# Rene_Panel_schematic.net
KiCad netlist of a schematic drawn in Altium Designer
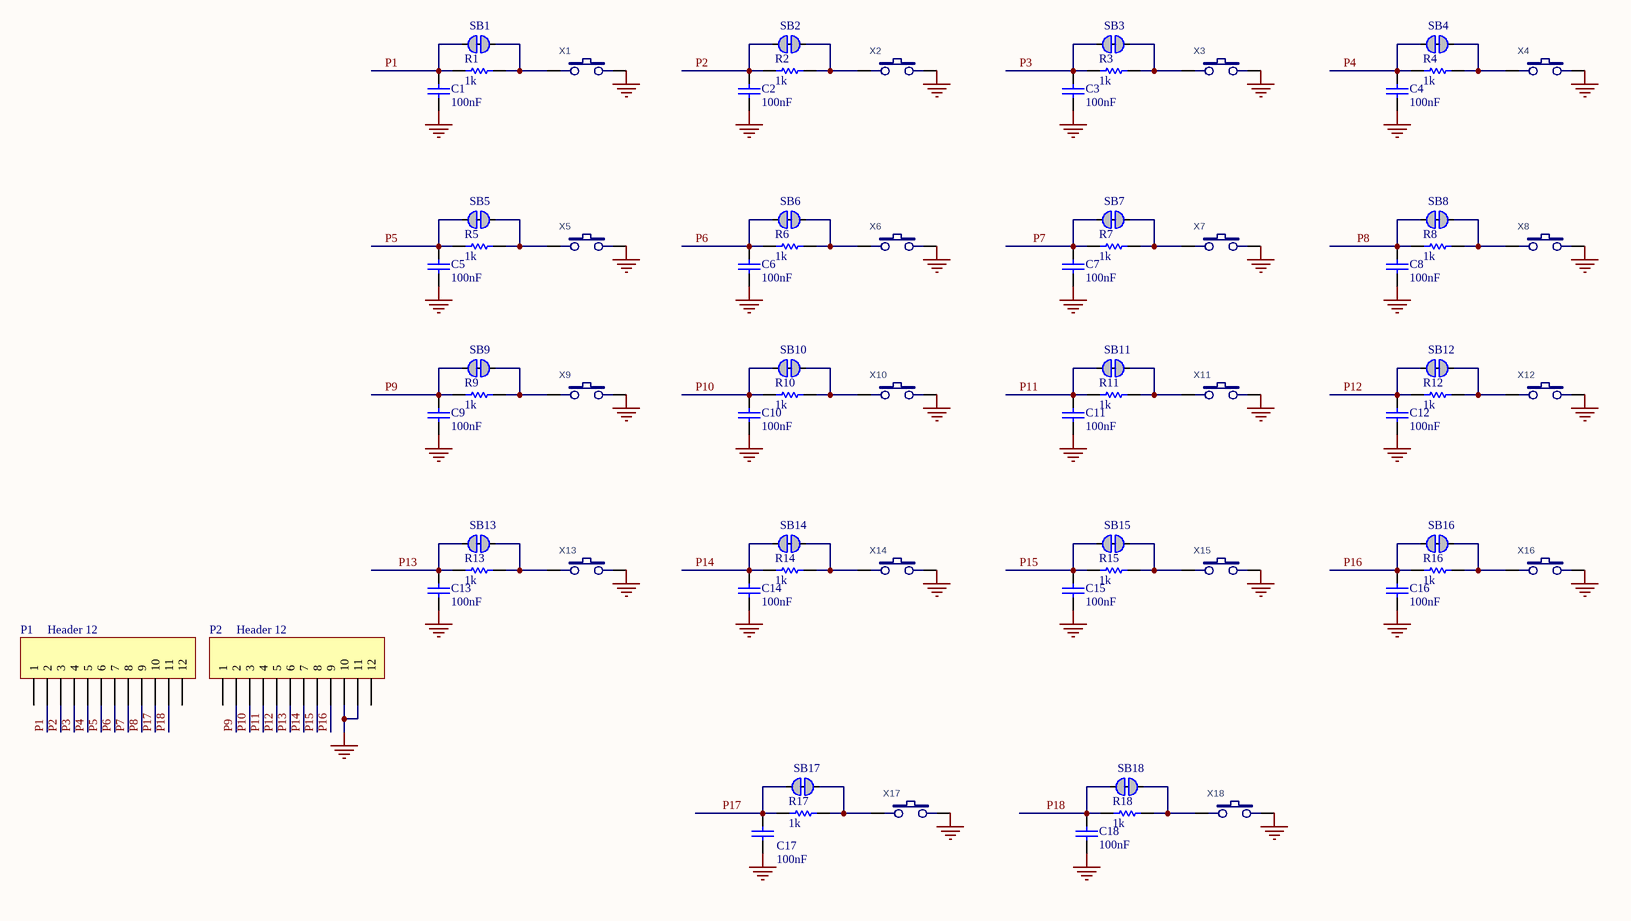
[diagram p0: Rene_Panel_schematic.SchDoc]

(export (version "E")
  (design (tool "Eeschema 10.0.6"))
  (components
    (comp (ref "C1")
      (value "100nF")
      (footprint "myParts:CAPA_0805")
      (description "100nF 0805")
      (fields (field (name "PARTNUMBER") "885012207072"))
      (libsource (lib "myParts") (part "Capacitor"))
    )
    (comp (ref "C2")
      (value "100nF")
      (footprint "myParts:CAPA_0805")
      (description "100nF 0805")
      (fields (field (name "PARTNUMBER") "885012207072"))
      (libsource (lib "myParts") (part "Capacitor"))
    )
    (comp (ref "C3")
      (value "100nF")
      (footprint "myParts:CAPA_0805")
      (description "100nF 0805")
      (fields (field (name "PARTNUMBER") "885012207072"))
      (libsource (lib "myParts") (part "Capacitor"))
    )
    (comp (ref "C4")
      (value "100nF")
      (footprint "myParts:CAPA_0805")
      (description "100nF 0805")
      (fields (field (name "PARTNUMBER") "885012207072"))
      (libsource (lib "myParts") (part "Capacitor"))
    )
    (comp (ref "C5")
      (value "100nF")
      (footprint "myParts:CAPA_0805")
      (description "100nF 0805")
      (fields (field (name "PARTNUMBER") "885012207072"))
      (libsource (lib "myParts") (part "Capacitor"))
    )
    (comp (ref "C6")
      (value "100nF")
      (footprint "myParts:CAPA_0805")
      (description "100nF 0805")
      (fields (field (name "PARTNUMBER") "885012207072"))
      (libsource (lib "myParts") (part "Capacitor"))
    )
    (comp (ref "C7")
      (value "100nF")
      (footprint "myParts:CAPA_0805")
      (description "100nF 0805")
      (fields (field (name "PARTNUMBER") "885012207072"))
      (libsource (lib "myParts") (part "Capacitor"))
    )
    (comp (ref "C8")
      (value "100nF")
      (footprint "myParts:CAPA_0805")
      (description "100nF 0805")
      (fields (field (name "PARTNUMBER") "885012207072"))
      (libsource (lib "myParts") (part "Capacitor"))
    )
    (comp (ref "C9")
      (value "100nF")
      (footprint "myParts:CAPA_0805")
      (description "100nF 0805")
      (fields (field (name "PARTNUMBER") "885012207072"))
      (libsource (lib "myParts") (part "Capacitor"))
    )
    (comp (ref "C10")
      (value "100nF")
      (footprint "myParts:CAPA_0805")
      (description "100nF 0805")
      (fields (field (name "PARTNUMBER") "885012207072"))
      (libsource (lib "myParts") (part "Capacitor"))
    )
    (comp (ref "C11")
      (value "100nF")
      (footprint "myParts:CAPA_0805")
      (description "100nF 0805")
      (fields (field (name "PARTNUMBER") "885012207072"))
      (libsource (lib "myParts") (part "Capacitor"))
    )
    (comp (ref "C12")
      (value "100nF")
      (footprint "myParts:CAPA_0805")
      (description "100nF 0805")
      (fields (field (name "PARTNUMBER") "885012207072"))
      (libsource (lib "myParts") (part "Capacitor"))
    )
    (comp (ref "C13")
      (value "100nF")
      (footprint "myParts:CAPA_0805")
      (description "100nF 0805")
      (fields (field (name "PARTNUMBER") "885012207072"))
      (libsource (lib "myParts") (part "Capacitor"))
    )
    (comp (ref "C14")
      (value "100nF")
      (footprint "myParts:CAPA_0805")
      (description "100nF 0805")
      (fields (field (name "PARTNUMBER") "885012207072"))
      (libsource (lib "myParts") (part "Capacitor"))
    )
    (comp (ref "C15")
      (value "100nF")
      (footprint "myParts:CAPA_0805")
      (description "100nF 0805")
      (fields (field (name "PARTNUMBER") "885012207072"))
      (libsource (lib "myParts") (part "Capacitor"))
    )
    (comp (ref "C16")
      (value "100nF")
      (footprint "myParts:CAPA_0805")
      (description "100nF 0805")
      (fields (field (name "PARTNUMBER") "885012207072"))
      (libsource (lib "myParts") (part "Capacitor"))
    )
    (comp (ref "C17")
      (value "100nF")
      (footprint "myParts:CAPA_0805")
      (description "100nF 0805")
      (fields (field (name "PARTNUMBER") "885012207072"))
      (libsource (lib "myParts") (part "Capacitor"))
    )
    (comp (ref "C18")
      (value "100nF")
      (footprint "myParts:CAPA_0805")
      (description "100nF 0805")
      (fields (field (name "PARTNUMBER") "885012207072"))
      (libsource (lib "myParts") (part "Capacitor"))
    )
    (comp (ref "P1")
      (value "Header 12")
      (footprint "myParts:LIST_1x12_SMD")
      (description "Header, 12-Pin")
      (fields (field (name "PUBLISHER") "Altium Limited"))
      (libsource (lib "Miscellaneous Connectors") (part "Header 12"))
    )
    (comp (ref "P2")
      (value "Header 12")
      (footprint "myParts:LIST_1x12_SMD")
      (description "Header, 12-Pin")
      (fields (field (name "PUBLISHER") "Altium Limited"))
      (libsource (lib "Miscellaneous Connectors") (part "Header 12"))
    )
    (comp (ref "R1")
      (value "1k")
      (footprint "myParts:RES_0805")
      (description "10k 0805")
      (fields (field (name "PARTNUMBER") "RR1220P-103-D") (field (name "MANUFACTURER") "Susumu"))
      (libsource (lib "myParts") (part "Resistor"))
    )
    (comp (ref "R2")
      (value "1k")
      (footprint "myParts:RES_0805")
      (description "10k 0805")
      (fields (field (name "PARTNUMBER") "RR1220P-103-D") (field (name "MANUFACTURER") "Susumu"))
      (libsource (lib "myParts") (part "Resistor"))
    )
    (comp (ref "R3")
      (value "1k")
      (footprint "myParts:RES_0805")
      (description "10k 0805")
      (fields (field (name "PARTNUMBER") "RR1220P-103-D") (field (name "MANUFACTURER") "Susumu"))
      (libsource (lib "myParts") (part "Resistor"))
    )
    (comp (ref "R4")
      (value "1k")
      (footprint "myParts:RES_0805")
      (description "10k 0805")
      (fields (field (name "PARTNUMBER") "RR1220P-103-D") (field (name "MANUFACTURER") "Susumu"))
      (libsource (lib "myParts") (part "Resistor"))
    )
    (comp (ref "R5")
      (value "1k")
      (footprint "myParts:RES_0805")
      (description "10k 0805")
      (fields (field (name "PARTNUMBER") "RR1220P-103-D") (field (name "MANUFACTURER") "Susumu"))
      (libsource (lib "myParts") (part "Resistor"))
    )
    (comp (ref "R6")
      (value "1k")
      (footprint "myParts:RES_0805")
      (description "10k 0805")
      (fields (field (name "PARTNUMBER") "RR1220P-103-D") (field (name "MANUFACTURER") "Susumu"))
      (libsource (lib "myParts") (part "Resistor"))
    )
    (comp (ref "R7")
      (value "1k")
      (footprint "myParts:RES_0805")
      (description "10k 0805")
      (fields (field (name "PARTNUMBER") "RR1220P-103-D") (field (name "MANUFACTURER") "Susumu"))
      (libsource (lib "myParts") (part "Resistor"))
    )
    (comp (ref "R8")
      (value "1k")
      (footprint "myParts:RES_0805")
      (description "10k 0805")
      (fields (field (name "PARTNUMBER") "RR1220P-103-D") (field (name "MANUFACTURER") "Susumu"))
      (libsource (lib "myParts") (part "Resistor"))
    )
    (comp (ref "R9")
      (value "1k")
      (footprint "myParts:RES_0805")
      (description "10k 0805")
      (fields (field (name "PARTNUMBER") "RR1220P-103-D") (field (name "MANUFACTURER") "Susumu"))
      (libsource (lib "myParts") (part "Resistor"))
    )
    (comp (ref "R10")
      (value "1k")
      (footprint "myParts:RES_0805")
      (description "10k 0805")
      (fields (field (name "PARTNUMBER") "RR1220P-103-D") (field (name "MANUFACTURER") "Susumu"))
      (libsource (lib "myParts") (part "Resistor"))
    )
    (comp (ref "R11")
      (value "1k")
      (footprint "myParts:RES_0805")
      (description "10k 0805")
      (fields (field (name "PARTNUMBER") "RR1220P-103-D") (field (name "MANUFACTURER") "Susumu"))
      (libsource (lib "myParts") (part "Resistor"))
    )
    (comp (ref "R12")
      (value "1k")
      (footprint "myParts:RES_0805")
      (description "10k 0805")
      (fields (field (name "PARTNUMBER") "RR1220P-103-D") (field (name "MANUFACTURER") "Susumu"))
      (libsource (lib "myParts") (part "Resistor"))
    )
    (comp (ref "R13")
      (value "1k")
      (footprint "myParts:RES_0805")
      (description "10k 0805")
      (fields (field (name "PARTNUMBER") "RR1220P-103-D") (field (name "MANUFACTURER") "Susumu"))
      (libsource (lib "myParts") (part "Resistor"))
    )
    (comp (ref "R14")
      (value "1k")
      (footprint "myParts:RES_0805")
      (description "10k 0805")
      (fields (field (name "PARTNUMBER") "RR1220P-103-D") (field (name "MANUFACTURER") "Susumu"))
      (libsource (lib "myParts") (part "Resistor"))
    )
    (comp (ref "R15")
      (value "1k")
      (footprint "myParts:RES_0805")
      (description "10k 0805")
      (fields (field (name "PARTNUMBER") "RR1220P-103-D") (field (name "MANUFACTURER") "Susumu"))
      (libsource (lib "myParts") (part "Resistor"))
    )
    (comp (ref "R16")
      (value "1k")
      (footprint "myParts:RES_0805")
      (description "10k 0805")
      (fields (field (name "PARTNUMBER") "RR1220P-103-D") (field (name "MANUFACTURER") "Susumu"))
      (libsource (lib "myParts") (part "Resistor"))
    )
    (comp (ref "R17")
      (value "1k")
      (footprint "myParts:RES_0805")
      (description "10k 0805")
      (fields (field (name "PARTNUMBER") "RR1220P-103-D") (field (name "MANUFACTURER") "Susumu"))
      (libsource (lib "myParts") (part "Resistor"))
    )
    (comp (ref "R18")
      (value "1k")
      (footprint "myParts:RES_0805")
      (description "10k 0805")
      (fields (field (name "PARTNUMBER") "RR1220P-103-D") (field (name "MANUFACTURER") "Susumu"))
      (libsource (lib "myParts") (part "Resistor"))
    )
    (comp (ref "SB1")
      (value "Solderbridge")
      (footprint "myParts:Solderbridge_Shorted")
      (description "Shorted Solderbridge")
      (fields
        (field (name "PART NUMBER") "Solderbridge Shorted")
        (field (name "PUBLISHER") "Nordic Semiconductor")
      )
      (libsource (lib "myParts") (part "SOLDERBRIDGE_SHORTED"))
    )
    (comp (ref "SB2")
      (value "Solderbridge")
      (footprint "myParts:Solderbridge_Shorted")
      (description "Shorted Solderbridge")
      (fields
        (field (name "PART NUMBER") "Solderbridge Shorted")
        (field (name "PUBLISHER") "Nordic Semiconductor")
      )
      (libsource (lib "myParts") (part "SOLDERBRIDGE_SHORTED"))
    )
    (comp (ref "SB3")
      (value "Solderbridge")
      (footprint "myParts:Solderbridge_Shorted")
      (description "Shorted Solderbridge")
      (fields
        (field (name "PART NUMBER") "Solderbridge Shorted")
        (field (name "PUBLISHER") "Nordic Semiconductor")
      )
      (libsource (lib "myParts") (part "SOLDERBRIDGE_SHORTED"))
    )
    (comp (ref "SB4")
      (value "Solderbridge")
      (footprint "myParts:Solderbridge_Shorted")
      (description "Shorted Solderbridge")
      (fields
        (field (name "PART NUMBER") "Solderbridge Shorted")
        (field (name "PUBLISHER") "Nordic Semiconductor")
      )
      (libsource (lib "myParts") (part "SOLDERBRIDGE_SHORTED"))
    )
    (comp (ref "SB5")
      (value "Solderbridge")
      (footprint "myParts:Solderbridge_Shorted")
      (description "Shorted Solderbridge")
      (fields
        (field (name "PART NUMBER") "Solderbridge Shorted")
        (field (name "PUBLISHER") "Nordic Semiconductor")
      )
      (libsource (lib "myParts") (part "SOLDERBRIDGE_SHORTED"))
    )
    (comp (ref "SB6")
      (value "Solderbridge")
      (footprint "myParts:Solderbridge_Shorted")
      (description "Shorted Solderbridge")
      (fields
        (field (name "PART NUMBER") "Solderbridge Shorted")
        (field (name "PUBLISHER") "Nordic Semiconductor")
      )
      (libsource (lib "myParts") (part "SOLDERBRIDGE_SHORTED"))
    )
    (comp (ref "SB7")
      (value "Solderbridge")
      (footprint "myParts:Solderbridge_Shorted")
      (description "Shorted Solderbridge")
      (fields
        (field (name "PART NUMBER") "Solderbridge Shorted")
        (field (name "PUBLISHER") "Nordic Semiconductor")
      )
      (libsource (lib "myParts") (part "SOLDERBRIDGE_SHORTED"))
    )
    (comp (ref "SB8")
      (value "Solderbridge")
      (footprint "myParts:Solderbridge_Shorted")
      (description "Shorted Solderbridge")
      (fields
        (field (name "PART NUMBER") "Solderbridge Shorted")
        (field (name "PUBLISHER") "Nordic Semiconductor")
      )
      (libsource (lib "myParts") (part "SOLDERBRIDGE_SHORTED"))
    )
    (comp (ref "SB9")
      (value "Solderbridge")
      (footprint "myParts:Solderbridge_Shorted")
      (description "Shorted Solderbridge")
      (fields
        (field (name "PART NUMBER") "Solderbridge Shorted")
        (field (name "PUBLISHER") "Nordic Semiconductor")
      )
      (libsource (lib "myParts") (part "SOLDERBRIDGE_SHORTED"))
    )
    (comp (ref "SB10")
      (value "Solderbridge")
      (footprint "myParts:Solderbridge_Shorted")
      (description "Shorted Solderbridge")
      (fields
        (field (name "PART NUMBER") "Solderbridge Shorted")
        (field (name "PUBLISHER") "Nordic Semiconductor")
      )
      (libsource (lib "myParts") (part "SOLDERBRIDGE_SHORTED"))
    )
    (comp (ref "SB11")
      (value "Solderbridge")
      (footprint "myParts:Solderbridge_Shorted")
      (description "Shorted Solderbridge")
      (fields
        (field (name "PART NUMBER") "Solderbridge Shorted")
        (field (name "PUBLISHER") "Nordic Semiconductor")
      )
      (libsource (lib "myParts") (part "SOLDERBRIDGE_SHORTED"))
    )
    (comp (ref "SB12")
      (value "Solderbridge")
      (footprint "myParts:Solderbridge_Shorted")
      (description "Shorted Solderbridge")
      (fields
        (field (name "PART NUMBER") "Solderbridge Shorted")
        (field (name "PUBLISHER") "Nordic Semiconductor")
      )
      (libsource (lib "myParts") (part "SOLDERBRIDGE_SHORTED"))
    )
    (comp (ref "SB13")
      (value "Solderbridge")
      (footprint "myParts:Solderbridge_Shorted")
      (description "Shorted Solderbridge")
      (fields
        (field (name "PART NUMBER") "Solderbridge Shorted")
        (field (name "PUBLISHER") "Nordic Semiconductor")
      )
      (libsource (lib "myParts") (part "SOLDERBRIDGE_SHORTED"))
    )
    (comp (ref "SB14")
      (value "Solderbridge")
      (footprint "myParts:Solderbridge_Shorted")
      (description "Shorted Solderbridge")
      (fields
        (field (name "PART NUMBER") "Solderbridge Shorted")
        (field (name "PUBLISHER") "Nordic Semiconductor")
      )
      (libsource (lib "myParts") (part "SOLDERBRIDGE_SHORTED"))
    )
    (comp (ref "SB15")
      (value "Solderbridge")
      (footprint "myParts:Solderbridge_Shorted")
      (description "Shorted Solderbridge")
      (fields
        (field (name "PART NUMBER") "Solderbridge Shorted")
        (field (name "PUBLISHER") "Nordic Semiconductor")
      )
      (libsource (lib "myParts") (part "SOLDERBRIDGE_SHORTED"))
    )
    (comp (ref "SB16")
      (value "Solderbridge")
      (footprint "myParts:Solderbridge_Shorted")
      (description "Shorted Solderbridge")
      (fields
        (field (name "PART NUMBER") "Solderbridge Shorted")
        (field (name "PUBLISHER") "Nordic Semiconductor")
      )
      (libsource (lib "myParts") (part "SOLDERBRIDGE_SHORTED"))
    )
    (comp (ref "SB17")
      (value "Solderbridge")
      (footprint "myParts:Solderbridge_Shorted")
      (description "Shorted Solderbridge")
      (fields
        (field (name "PART NUMBER") "Solderbridge Shorted")
        (field (name "PUBLISHER") "Nordic Semiconductor")
      )
      (libsource (lib "myParts") (part "SOLDERBRIDGE_SHORTED"))
    )
    (comp (ref "SB18")
      (value "Solderbridge")
      (footprint "myParts:Solderbridge_Shorted")
      (description "Shorted Solderbridge")
      (fields
        (field (name "PART NUMBER") "Solderbridge Shorted")
        (field (name "PUBLISHER") "Nordic Semiconductor")
      )
      (libsource (lib "myParts") (part "SOLDERBRIDGE_SHORTED"))
    )
    (comp (ref "X1")
      (value "101-0124-EV")
      (footprint "myParts:Tactile_switch_12mm_TH")
      (description "Push Button SMD EVPAWBA2A")
      (fields (field (name "MANUFACTURER") "Mountain Switch"))
      (libsource (lib "Basslet") (part "SWITCH/Push Button-EVPAWBA2A"))
    )
    (comp (ref "X2")
      (value "101-0124-EV")
      (footprint "Tactile_switch_12mm_TH")
      (description "Push Button SMD EVPAWBA2A")
      (fields (field (name "MANUFACTURER") "Mountain Switch"))
      (libsource (lib "Basslet") (part "SWITCH/Push Button-EVPAWBA2A"))
    )
    (comp (ref "X3")
      (value "101-0124-EV")
      (footprint "Tactile_switch_12mm_TH")
      (description "Push Button SMD EVPAWBA2A")
      (fields (field (name "MANUFACTURER") "Mountain Switch"))
      (libsource (lib "Basslet") (part "SWITCH/Push Button-EVPAWBA2A"))
    )
    (comp (ref "X4")
      (value "101-0124-EV")
      (footprint "Tactile_switch_12mm_TH")
      (description "Push Button SMD EVPAWBA2A")
      (fields (field (name "MANUFACTURER") "Mountain Switch"))
      (libsource (lib "Basslet") (part "SWITCH/Push Button-EVPAWBA2A"))
    )
    (comp (ref "X5")
      (value "101-0124-EV")
      (footprint "Tactile_switch_12mm_TH")
      (description "Push Button SMD EVPAWBA2A")
      (fields (field (name "MANUFACTURER") "Mountain Switch"))
      (libsource (lib "Basslet") (part "SWITCH/Push Button-EVPAWBA2A"))
    )
    (comp (ref "X6")
      (value "101-0124-EV")
      (footprint "Tactile_switch_12mm_TH")
      (description "Push Button SMD EVPAWBA2A")
      (fields (field (name "MANUFACTURER") "Mountain Switch"))
      (libsource (lib "Basslet") (part "SWITCH/Push Button-EVPAWBA2A"))
    )
    (comp (ref "X7")
      (value "101-0124-EV")
      (footprint "Tactile_switch_12mm_TH")
      (description "Push Button SMD EVPAWBA2A")
      (fields (field (name "MANUFACTURER") "Mountain Switch"))
      (libsource (lib "Basslet") (part "SWITCH/Push Button-EVPAWBA2A"))
    )
    (comp (ref "X8")
      (value "101-0124-EV")
      (footprint "Tactile_switch_12mm_TH")
      (description "Push Button SMD EVPAWBA2A")
      (fields (field (name "MANUFACTURER") "Mountain Switch"))
      (libsource (lib "Basslet") (part "SWITCH/Push Button-EVPAWBA2A"))
    )
    (comp (ref "X9")
      (value "101-0124-EV")
      (footprint "Tactile_switch_12mm_TH")
      (description "Push Button SMD EVPAWBA2A")
      (fields (field (name "MANUFACTURER") "Mountain Switch"))
      (libsource (lib "Basslet") (part "SWITCH/Push Button-EVPAWBA2A"))
    )
    (comp (ref "X10")
      (value "101-0124-EV")
      (footprint "Tactile_switch_12mm_TH")
      (description "Push Button SMD EVPAWBA2A")
      (fields (field (name "MANUFACTURER") "Mountain Switch"))
      (libsource (lib "Basslet") (part "SWITCH/Push Button-EVPAWBA2A"))
    )
    (comp (ref "X11")
      (value "101-0124-EV")
      (footprint "Tactile_switch_12mm_TH")
      (description "Push Button SMD EVPAWBA2A")
      (fields (field (name "MANUFACTURER") "Mountain Switch"))
      (libsource (lib "Basslet") (part "SWITCH/Push Button-EVPAWBA2A"))
    )
    (comp (ref "X12")
      (value "101-0124-EV")
      (footprint "Tactile_switch_12mm_TH")
      (description "Push Button SMD EVPAWBA2A")
      (fields (field (name "MANUFACTURER") "Mountain Switch"))
      (libsource (lib "Basslet") (part "SWITCH/Push Button-EVPAWBA2A"))
    )
    (comp (ref "X13")
      (value "101-0124-EV")
      (footprint "Tactile_switch_12mm_TH")
      (description "Push Button SMD EVPAWBA2A")
      (fields (field (name "MANUFACTURER") "Mountain Switch"))
      (libsource (lib "Basslet") (part "SWITCH/Push Button-EVPAWBA2A"))
    )
    (comp (ref "X14")
      (value "101-0124-EV")
      (footprint "Tactile_switch_12mm_TH")
      (description "Push Button SMD EVPAWBA2A")
      (fields (field (name "MANUFACTURER") "Mountain Switch"))
      (libsource (lib "Basslet") (part "SWITCH/Push Button-EVPAWBA2A"))
    )
    (comp (ref "X15")
      (value "101-0124-EV")
      (footprint "Tactile_switch_12mm_TH")
      (description "Push Button SMD EVPAWBA2A")
      (fields (field (name "MANUFACTURER") "Mountain Switch"))
      (libsource (lib "Basslet") (part "SWITCH/Push Button-EVPAWBA2A"))
    )
    (comp (ref "X16")
      (value "101-0124-EV")
      (footprint "Tactile_switch_12mm_TH")
      (description "Push Button SMD EVPAWBA2A")
      (fields (field (name "MANUFACTURER") "Mountain Switch"))
      (libsource (lib "Basslet") (part "SWITCH/Push Button-EVPAWBA2A"))
    )
    (comp (ref "X17")
      (value "PTS645SM43SMTR 92 LFS")
      (footprint "myParts:Tactile_switch_6mm_TH")
      (description "Push Button SMD EVPAWBA2A")
      (fields (field (name "MANUFACTURER") "C&K Components"))
      (libsource (lib "Basslet") (part "SWITCH/Push Button-EVPAWBA2A"))
    )
    (comp (ref "X18")
      (value "PTS645SM43SMTR 92 LFS")
      (footprint "myParts:Tactile_switch_6mm_TH")
      (description "Push Button SMD EVPAWBA2A")
      (fields (field (name "MANUFACTURER") "C&K Components"))
      (libsource (lib "Basslet") (part "SWITCH/Push Button-EVPAWBA2A"))
    )
  )
  (nets
    (net (code "1") (name "/P1") (class "Default")
      (node (ref "C1") (pin "2") (pinfunction "2_2") (pintype "passive"))
      (node (ref "P1") (pin "2") (pinfunction "2_2") (pintype "passive"))
      (node (ref "R1") (pin "1") (pinfunction "1_1") (pintype "passive"))
      (node (ref "SB1") (pin "2") (pinfunction "1_2") (pintype "passive"))
    )
    (net (code "2") (name "/P2") (class "Default")
      (node (ref "C2") (pin "2") (pinfunction "2_2") (pintype "passive"))
      (node (ref "P1") (pin "3") (pinfunction "3_3") (pintype "passive"))
      (node (ref "R2") (pin "1") (pinfunction "1_1") (pintype "passive"))
      (node (ref "SB2") (pin "2") (pinfunction "1_2") (pintype "passive"))
    )
    (net (code "3") (name "/P3") (class "Default")
      (node (ref "C3") (pin "2") (pinfunction "2_2") (pintype "passive"))
      (node (ref "P1") (pin "4") (pinfunction "4_4") (pintype "passive"))
      (node (ref "R3") (pin "1") (pinfunction "1_1") (pintype "passive"))
      (node (ref "SB3") (pin "2") (pinfunction "1_2") (pintype "passive"))
    )
    (net (code "4") (name "/P4") (class "Default")
      (node (ref "C4") (pin "2") (pinfunction "2_2") (pintype "passive"))
      (node (ref "P1") (pin "5") (pinfunction "5_5") (pintype "passive"))
      (node (ref "R4") (pin "1") (pinfunction "1_1") (pintype "passive"))
      (node (ref "SB4") (pin "2") (pinfunction "1_2") (pintype "passive"))
    )
    (net (code "5") (name "/P5") (class "Default")
      (node (ref "C5") (pin "2") (pinfunction "2_2") (pintype "passive"))
      (node (ref "P1") (pin "6") (pinfunction "6_6") (pintype "passive"))
      (node (ref "R5") (pin "1") (pinfunction "1_1") (pintype "passive"))
      (node (ref "SB5") (pin "2") (pinfunction "1_2") (pintype "passive"))
    )
    (net (code "6") (name "/P6") (class "Default")
      (node (ref "C6") (pin "2") (pinfunction "2_2") (pintype "passive"))
      (node (ref "P1") (pin "7") (pinfunction "7_7") (pintype "passive"))
      (node (ref "R6") (pin "1") (pinfunction "1_1") (pintype "passive"))
      (node (ref "SB6") (pin "2") (pinfunction "1_2") (pintype "passive"))
    )
    (net (code "7") (name "/P7") (class "Default")
      (node (ref "C7") (pin "2") (pinfunction "2_2") (pintype "passive"))
      (node (ref "P1") (pin "8") (pinfunction "8_8") (pintype "passive"))
      (node (ref "R7") (pin "1") (pinfunction "1_1") (pintype "passive"))
      (node (ref "SB7") (pin "2") (pinfunction "1_2") (pintype "passive"))
    )
    (net (code "8") (name "/P8") (class "Default")
      (node (ref "C8") (pin "2") (pinfunction "2_2") (pintype "passive"))
      (node (ref "P1") (pin "9") (pinfunction "9_9") (pintype "passive"))
      (node (ref "R8") (pin "1") (pinfunction "1_1") (pintype "passive"))
      (node (ref "SB8") (pin "2") (pinfunction "1_2") (pintype "passive"))
    )
    (net (code "9") (name "/P9") (class "Default")
      (node (ref "C9") (pin "2") (pinfunction "2_2") (pintype "passive"))
      (node (ref "P2") (pin "2") (pinfunction "2_2") (pintype "passive"))
      (node (ref "R9") (pin "1") (pinfunction "1_1") (pintype "passive"))
      (node (ref "SB9") (pin "2") (pinfunction "1_2") (pintype "passive"))
    )
    (net (code "10") (name "/P10") (class "Default")
      (node (ref "C10") (pin "2") (pinfunction "2_2") (pintype "passive"))
      (node (ref "P2") (pin "3") (pinfunction "3_3") (pintype "passive"))
      (node (ref "R10") (pin "1") (pinfunction "1_1") (pintype "passive"))
      (node (ref "SB10") (pin "2") (pinfunction "1_2") (pintype "passive"))
    )
    (net (code "11") (name "/P11") (class "Default")
      (node (ref "C11") (pin "2") (pinfunction "2_2") (pintype "passive"))
      (node (ref "P2") (pin "4") (pinfunction "4_4") (pintype "passive"))
      (node (ref "R11") (pin "1") (pinfunction "1_1") (pintype "passive"))
      (node (ref "SB11") (pin "2") (pinfunction "1_2") (pintype "passive"))
    )
    (net (code "12") (name "/P12") (class "Default")
      (node (ref "C12") (pin "2") (pinfunction "2_2") (pintype "passive"))
      (node (ref "P2") (pin "5") (pinfunction "5_5") (pintype "passive"))
      (node (ref "R12") (pin "1") (pinfunction "1_1") (pintype "passive"))
      (node (ref "SB12") (pin "2") (pinfunction "1_2") (pintype "passive"))
    )
    (net (code "13") (name "/P13") (class "Default")
      (node (ref "C13") (pin "2") (pinfunction "2_2") (pintype "passive"))
      (node (ref "P2") (pin "6") (pinfunction "6_6") (pintype "passive"))
      (node (ref "R13") (pin "1") (pinfunction "1_1") (pintype "passive"))
      (node (ref "SB13") (pin "2") (pinfunction "1_2") (pintype "passive"))
    )
    (net (code "14") (name "/P14") (class "Default")
      (node (ref "C14") (pin "2") (pinfunction "2_2") (pintype "passive"))
      (node (ref "P2") (pin "7") (pinfunction "7_7") (pintype "passive"))
      (node (ref "R14") (pin "1") (pinfunction "1_1") (pintype "passive"))
      (node (ref "SB14") (pin "2") (pinfunction "1_2") (pintype "passive"))
    )
    (net (code "15") (name "/P15") (class "Default")
      (node (ref "C15") (pin "2") (pinfunction "2_2") (pintype "passive"))
      (node (ref "P2") (pin "8") (pinfunction "8_8") (pintype "passive"))
      (node (ref "R15") (pin "1") (pinfunction "1_1") (pintype "passive"))
      (node (ref "SB15") (pin "2") (pinfunction "1_2") (pintype "passive"))
    )
    (net (code "16") (name "/P16") (class "Default")
      (node (ref "C16") (pin "2") (pinfunction "2_2") (pintype "passive"))
      (node (ref "P2") (pin "9") (pinfunction "9_9") (pintype "passive"))
      (node (ref "R16") (pin "1") (pinfunction "1_1") (pintype "passive"))
      (node (ref "SB16") (pin "2") (pinfunction "1_2") (pintype "passive"))
    )
    (net (code "17") (name "/P17") (class "Default")
      (node (ref "C17") (pin "2") (pinfunction "2_2") (pintype "passive"))
      (node (ref "P1") (pin "10") (pinfunction "10_10") (pintype "passive"))
      (node (ref "R17") (pin "1") (pinfunction "1_1") (pintype "passive"))
      (node (ref "SB17") (pin "2") (pinfunction "1_2") (pintype "passive"))
    )
    (net (code "18") (name "/P18") (class "Default")
      (node (ref "C18") (pin "2") (pinfunction "2_2") (pintype "passive"))
      (node (ref "P1") (pin "11") (pinfunction "11_11") (pintype "passive"))
      (node (ref "R18") (pin "1") (pinfunction "1_1") (pintype "passive"))
      (node (ref "SB18") (pin "2") (pinfunction "1_2") (pintype "passive"))
    )
    (net (code "19") (name "GND") (class "Default")
      (node (ref "C1") (pin "1") (pinfunction "1_1") (pintype "passive"))
      (node (ref "C10") (pin "1") (pinfunction "1_1") (pintype "passive"))
      (node (ref "C11") (pin "1") (pinfunction "1_1") (pintype "passive"))
      (node (ref "C12") (pin "1") (pinfunction "1_1") (pintype "passive"))
      (node (ref "C13") (pin "1") (pinfunction "1_1") (pintype "passive"))
      (node (ref "C14") (pin "1") (pinfunction "1_1") (pintype "passive"))
      (node (ref "C15") (pin "1") (pinfunction "1_1") (pintype "passive"))
      (node (ref "C16") (pin "1") (pinfunction "1_1") (pintype "passive"))
      (node (ref "C17") (pin "1") (pinfunction "1_1") (pintype "passive"))
      (node (ref "C18") (pin "1") (pinfunction "1_1") (pintype "passive"))
      (node (ref "C2") (pin "1") (pinfunction "1_1") (pintype "passive"))
      (node (ref "C3") (pin "1") (pinfunction "1_1") (pintype "passive"))
      (node (ref "C4") (pin "1") (pinfunction "1_1") (pintype "passive"))
      (node (ref "C5") (pin "1") (pinfunction "1_1") (pintype "passive"))
      (node (ref "C6") (pin "1") (pinfunction "1_1") (pintype "passive"))
      (node (ref "C7") (pin "1") (pinfunction "1_1") (pintype "passive"))
      (node (ref "C8") (pin "1") (pinfunction "1_1") (pintype "passive"))
      (node (ref "C9") (pin "1") (pinfunction "1_1") (pintype "passive"))
      (node (ref "P2") (pin "10") (pinfunction "10_10") (pintype "passive"))
      (node (ref "P2") (pin "11") (pinfunction "11_11") (pintype "passive"))
      (node (ref "X1") (pin "2") (pinfunction "B_2") (pintype "passive"))
      (node (ref "X10") (pin "2") (pinfunction "B_2") (pintype "passive"))
      (node (ref "X11") (pin "2") (pinfunction "B_2") (pintype "passive"))
      (node (ref "X12") (pin "2") (pinfunction "B_2") (pintype "passive"))
      (node (ref "X13") (pin "2") (pinfunction "B_2") (pintype "passive"))
      (node (ref "X14") (pin "2") (pinfunction "B_2") (pintype "passive"))
      (node (ref "X15") (pin "2") (pinfunction "B_2") (pintype "passive"))
      (node (ref "X16") (pin "2") (pinfunction "B_2") (pintype "passive"))
      (node (ref "X17") (pin "2") (pinfunction "B_2") (pintype "passive"))
      (node (ref "X18") (pin "2") (pinfunction "B_2") (pintype "passive"))
      (node (ref "X2") (pin "2") (pinfunction "B_2") (pintype "passive"))
      (node (ref "X3") (pin "2") (pinfunction "B_2") (pintype "passive"))
      (node (ref "X4") (pin "2") (pinfunction "B_2") (pintype "passive"))
      (node (ref "X5") (pin "2") (pinfunction "B_2") (pintype "passive"))
      (node (ref "X6") (pin "2") (pinfunction "B_2") (pintype "passive"))
      (node (ref "X7") (pin "2") (pinfunction "B_2") (pintype "passive"))
      (node (ref "X8") (pin "2") (pinfunction "B_2") (pintype "passive"))
      (node (ref "X9") (pin "2") (pinfunction "B_2") (pintype "passive"))
    )
    (net (code "20") (name "Net-(SB1-0)") (class "Default")
      (node (ref "R1") (pin "2") (pinfunction "2_2") (pintype "passive"))
      (node (ref "SB1") (pin "1") (pinfunction "0_1") (pintype "passive"))
      (node (ref "X1") (pin "1") (pinfunction "A_1") (pintype "passive"))
    )
    (net (code "21") (name "Net-(SB2-0)") (class "Default")
      (node (ref "R2") (pin "2") (pinfunction "2_2") (pintype "passive"))
      (node (ref "SB2") (pin "1") (pinfunction "0_1") (pintype "passive"))
      (node (ref "X2") (pin "1") (pinfunction "A_1") (pintype "passive"))
    )
    (net (code "22") (name "Net-(SB3-0)") (class "Default")
      (node (ref "R3") (pin "2") (pinfunction "2_2") (pintype "passive"))
      (node (ref "SB3") (pin "1") (pinfunction "0_1") (pintype "passive"))
      (node (ref "X3") (pin "1") (pinfunction "A_1") (pintype "passive"))
    )
    (net (code "23") (name "Net-(SB4-0)") (class "Default")
      (node (ref "R4") (pin "2") (pinfunction "2_2") (pintype "passive"))
      (node (ref "SB4") (pin "1") (pinfunction "0_1") (pintype "passive"))
      (node (ref "X4") (pin "1") (pinfunction "A_1") (pintype "passive"))
    )
    (net (code "24") (name "Net-(SB5-0)") (class "Default")
      (node (ref "R5") (pin "2") (pinfunction "2_2") (pintype "passive"))
      (node (ref "SB5") (pin "1") (pinfunction "0_1") (pintype "passive"))
      (node (ref "X5") (pin "1") (pinfunction "A_1") (pintype "passive"))
    )
    (net (code "25") (name "Net-(SB6-0)") (class "Default")
      (node (ref "R6") (pin "2") (pinfunction "2_2") (pintype "passive"))
      (node (ref "SB6") (pin "1") (pinfunction "0_1") (pintype "passive"))
      (node (ref "X6") (pin "1") (pinfunction "A_1") (pintype "passive"))
    )
    (net (code "26") (name "Net-(SB7-0)") (class "Default")
      (node (ref "R7") (pin "2") (pinfunction "2_2") (pintype "passive"))
      (node (ref "SB7") (pin "1") (pinfunction "0_1") (pintype "passive"))
      (node (ref "X7") (pin "1") (pinfunction "A_1") (pintype "passive"))
    )
    (net (code "27") (name "Net-(SB8-0)") (class "Default")
      (node (ref "R8") (pin "2") (pinfunction "2_2") (pintype "passive"))
      (node (ref "SB8") (pin "1") (pinfunction "0_1") (pintype "passive"))
      (node (ref "X8") (pin "1") (pinfunction "A_1") (pintype "passive"))
    )
    (net (code "28") (name "Net-(SB9-0)") (class "Default")
      (node (ref "R9") (pin "2") (pinfunction "2_2") (pintype "passive"))
      (node (ref "SB9") (pin "1") (pinfunction "0_1") (pintype "passive"))
      (node (ref "X9") (pin "1") (pinfunction "A_1") (pintype "passive"))
    )
    (net (code "29") (name "Net-(SB10-0)") (class "Default")
      (node (ref "R10") (pin "2") (pinfunction "2_2") (pintype "passive"))
      (node (ref "SB10") (pin "1") (pinfunction "0_1") (pintype "passive"))
      (node (ref "X10") (pin "1") (pinfunction "A_1") (pintype "passive"))
    )
    (net (code "30") (name "Net-(SB11-0)") (class "Default")
      (node (ref "R11") (pin "2") (pinfunction "2_2") (pintype "passive"))
      (node (ref "SB11") (pin "1") (pinfunction "0_1") (pintype "passive"))
      (node (ref "X11") (pin "1") (pinfunction "A_1") (pintype "passive"))
    )
    (net (code "31") (name "Net-(SB12-0)") (class "Default")
      (node (ref "R12") (pin "2") (pinfunction "2_2") (pintype "passive"))
      (node (ref "SB12") (pin "1") (pinfunction "0_1") (pintype "passive"))
      (node (ref "X12") (pin "1") (pinfunction "A_1") (pintype "passive"))
    )
    (net (code "32") (name "Net-(SB13-0)") (class "Default")
      (node (ref "R13") (pin "2") (pinfunction "2_2") (pintype "passive"))
      (node (ref "SB13") (pin "1") (pinfunction "0_1") (pintype "passive"))
      (node (ref "X13") (pin "1") (pinfunction "A_1") (pintype "passive"))
    )
    (net (code "33") (name "Net-(SB14-0)") (class "Default")
      (node (ref "R14") (pin "2") (pinfunction "2_2") (pintype "passive"))
      (node (ref "SB14") (pin "1") (pinfunction "0_1") (pintype "passive"))
      (node (ref "X14") (pin "1") (pinfunction "A_1") (pintype "passive"))
    )
    (net (code "34") (name "Net-(SB15-0)") (class "Default")
      (node (ref "R15") (pin "2") (pinfunction "2_2") (pintype "passive"))
      (node (ref "SB15") (pin "1") (pinfunction "0_1") (pintype "passive"))
      (node (ref "X15") (pin "1") (pinfunction "A_1") (pintype "passive"))
    )
    (net (code "35") (name "Net-(SB16-0)") (class "Default")
      (node (ref "R16") (pin "2") (pinfunction "2_2") (pintype "passive"))
      (node (ref "SB16") (pin "1") (pinfunction "0_1") (pintype "passive"))
      (node (ref "X16") (pin "1") (pinfunction "A_1") (pintype "passive"))
    )
    (net (code "36") (name "Net-(SB17-0)") (class "Default")
      (node (ref "R17") (pin "2") (pinfunction "2_2") (pintype "passive"))
      (node (ref "SB17") (pin "1") (pinfunction "0_1") (pintype "passive"))
      (node (ref "X17") (pin "1") (pinfunction "A_1") (pintype "passive"))
    )
    (net (code "37") (name "Net-(SB18-0)") (class "Default")
      (node (ref "R18") (pin "2") (pinfunction "2_2") (pintype "passive"))
      (node (ref "SB18") (pin "1") (pinfunction "0_1") (pintype "passive"))
      (node (ref "X18") (pin "1") (pinfunction "A_1") (pintype "passive"))
    )
    (net (code "38") (name "unconnected-(P1-Pad1)") (class "Default")
      (node (ref "P1") (pin "1") (pinfunction "1_1") (pintype "passive"))
    )
    (net (code "39") (name "unconnected-(P1-Pad12)") (class "Default")
      (node (ref "P1") (pin "12") (pinfunction "12_12") (pintype "passive"))
    )
    (net (code "40") (name "unconnected-(P2-Pad1)") (class "Default")
      (node (ref "P2") (pin "1") (pinfunction "1_1") (pintype "passive"))
    )
    (net (code "41") (name "unconnected-(P2-Pad12)") (class "Default")
      (node (ref "P2") (pin "12") (pinfunction "12_12") (pintype "passive"))
    )
  )
)
